# 04B-356.net
KiCad netlist of a schematic drawn in EAGLE
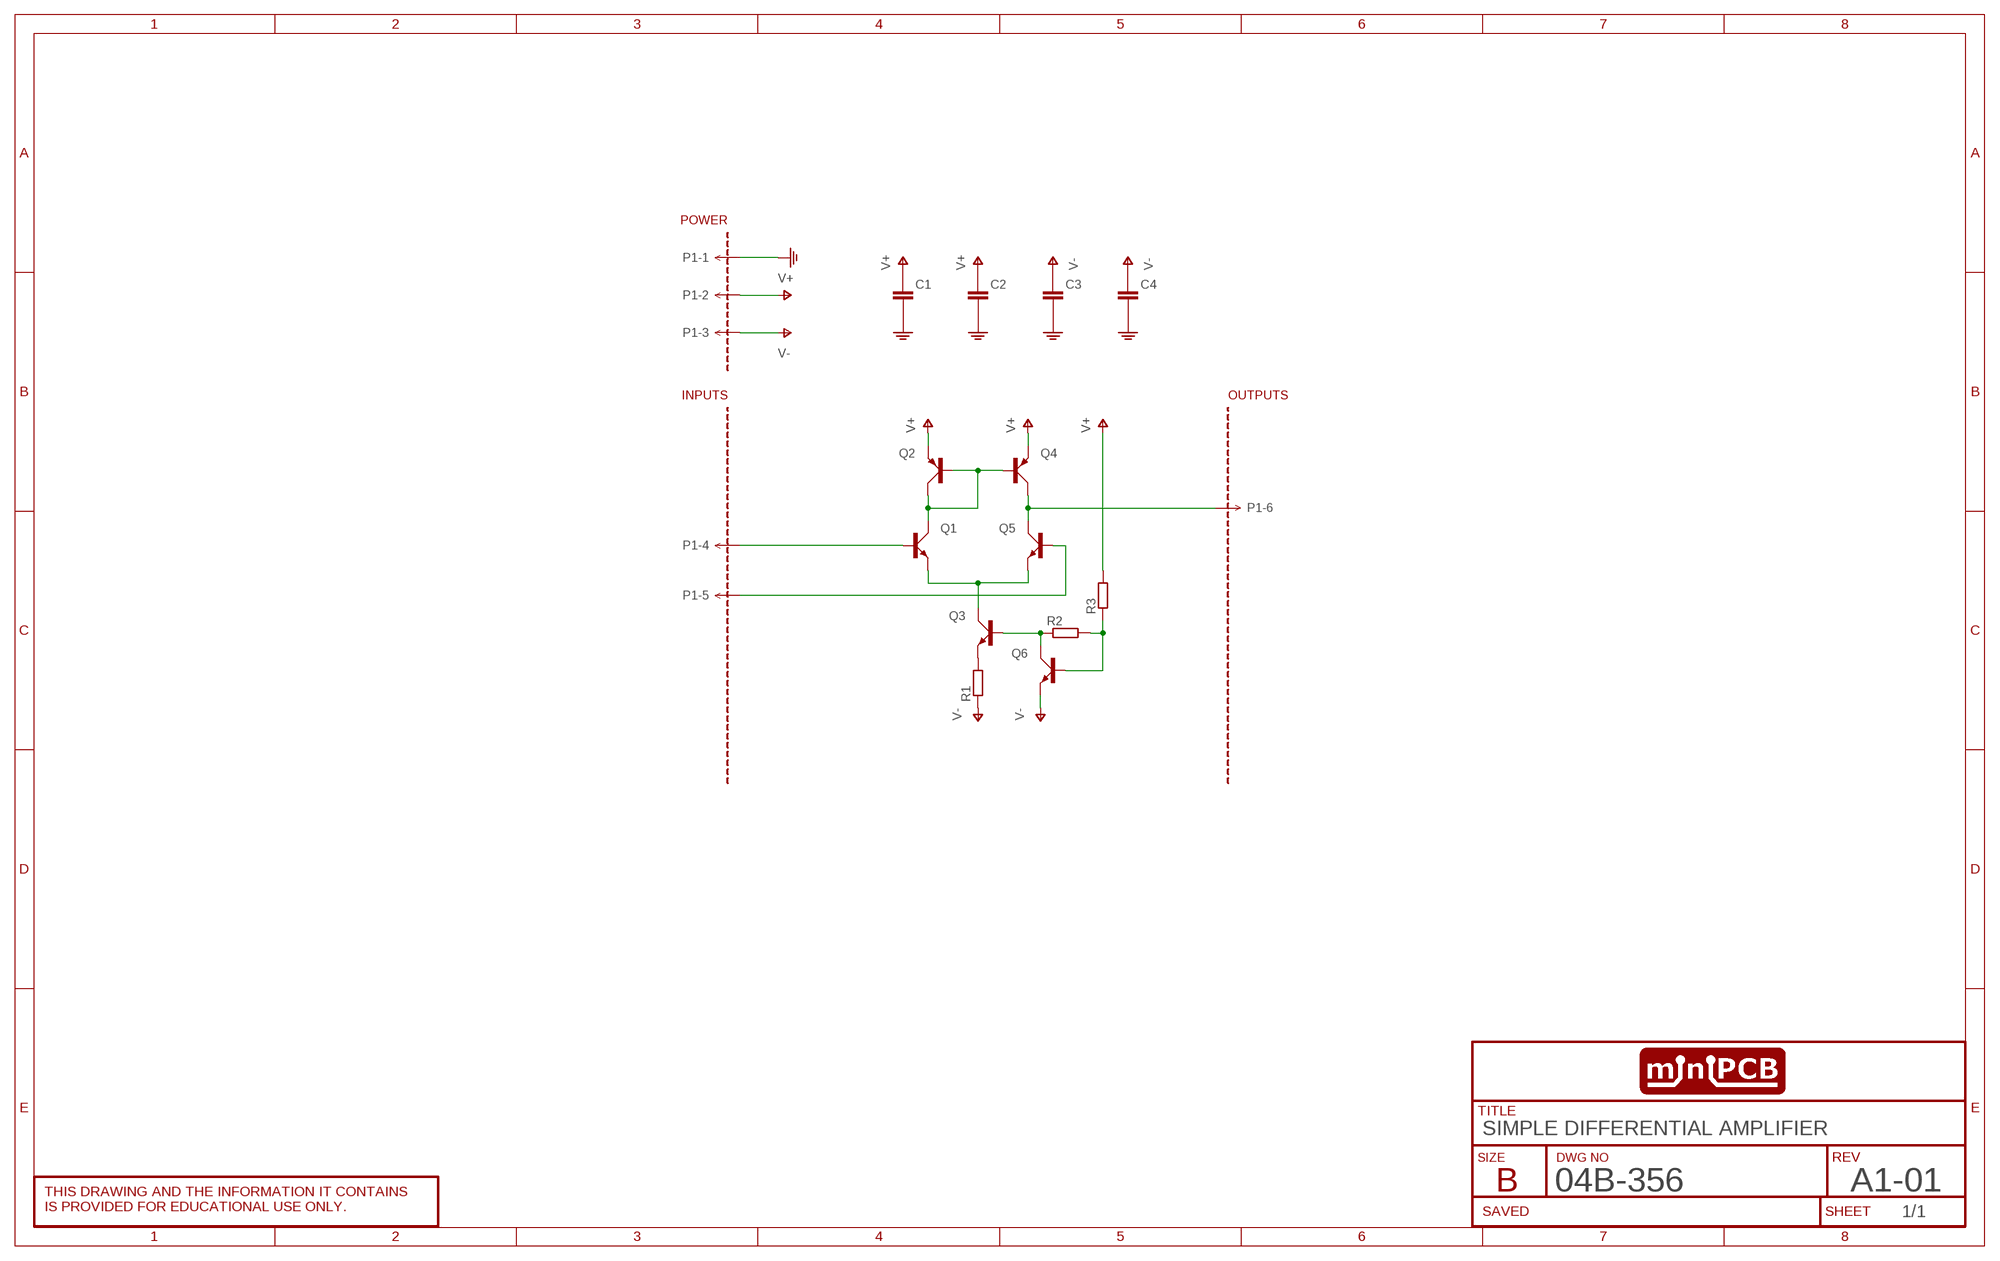
[diagram p0: schematic, sheet 1]

(export (version "E")
  (design (tool "Eeschema 10.0.6"))
  (components
    (comp (ref "C1")
      (value "CAPACITORSMD")
      (footprint "eagle-import:C0805")
      (libsource (lib "eagle-import") (part "CAPACITORSMD"))
    )
    (comp (ref "C2")
      (value "CAPACITORSMD")
      (footprint "eagle-import:C0805")
      (libsource (lib "eagle-import") (part "CAPACITORSMD"))
    )
    (comp (ref "C3")
      (value "CAPACITORSMD")
      (footprint "eagle-import:C0805")
      (libsource (lib "eagle-import") (part "CAPACITORSMD"))
    )
    (comp (ref "C4")
      (value "CAPACITORSMD")
      (footprint "eagle-import:C0805")
      (libsource (lib "eagle-import") (part "CAPACITORSMD"))
    )
    (comp (ref "P1")
      (value "MINIPCB_6P")
      (footprint "eagle-import:PINS_6")
      (libsource (lib "eagle-import") (part "MINIPCB_6P"))
    )
    (comp (ref "PCB1")
      (value "MINIPCB_0PPCB33-20")
      (footprint "eagle-import:PCB33-20")
      (fields (field (name "PART_NUMBER") "04B-356") (field (name "TITLE") "SIMPLE DIFF. AMP."))
      (libsource (lib "eagle-import") (part "MINIPCB_0PPCB33-20"))
    )
    (comp (ref "Q1")
      (value "BJT_NPNBEC")
      (footprint "eagle-import:SOT23")
      (libsource (lib "eagle-import") (part "BJT_NPNBEC"))
    )
    (comp (ref "Q2")
      (value "BJT_PNPBEC")
      (footprint "eagle-import:SOT23")
      (libsource (lib "eagle-import") (part "BJT_PNPBEC"))
    )
    (comp (ref "Q3")
      (value "BJT_NPNBEC")
      (footprint "eagle-import:SOT23")
      (libsource (lib "eagle-import") (part "BJT_NPNBEC"))
    )
    (comp (ref "Q4")
      (value "BJT_PNPBEC")
      (footprint "eagle-import:SOT23")
      (libsource (lib "eagle-import") (part "BJT_PNPBEC"))
    )
    (comp (ref "Q5")
      (value "BJT_NPNBEC")
      (footprint "eagle-import:SOT23")
      (libsource (lib "eagle-import") (part "BJT_NPNBEC"))
    )
    (comp (ref "Q6")
      (value "BJT_NPNBEC")
      (footprint "eagle-import:SOT23")
      (libsource (lib "eagle-import") (part "BJT_NPNBEC"))
    )
    (comp (ref "R1")
      (value "RESISTORSMD")
      (footprint "eagle-import:R0805")
      (libsource (lib "eagle-import") (part "RESISTORSMD"))
    )
    (comp (ref "R2")
      (value "RESISTORSMD")
      (footprint "eagle-import:R0805")
      (libsource (lib "eagle-import") (part "RESISTORSMD"))
    )
    (comp (ref "R3")
      (value "RESISTORSMD")
      (footprint "eagle-import:R0805")
      (libsource (lib "eagle-import") (part "RESISTORSMD"))
    )
  )
  (nets
    (net (code "1") (name "GND") (class "Default")
      (node (ref "C1") (pin "2ASDF") (pinfunction "-_2ASDF") (pintype "passive"))
      (node (ref "C2") (pin "2ASDF") (pinfunction "-_2ASDF") (pintype "passive"))
      (node (ref "C3") (pin "2ASDF") (pinfunction "-_2ASDF") (pintype "passive"))
      (node (ref "C4") (pin "2ASDF") (pinfunction "-_2ASDF") (pintype "passive"))
      (node (ref "P1") (pin "1") (pinfunction "1_1") (pintype "bidirectional"))
    )
    (net (code "2") (name "Net-(P1D-1)") (class "Default")
      (node (ref "P1") (pin "4") (pinfunction "1_4") (pintype "bidirectional"))
      (node (ref "Q1") (pin "1") (pinfunction "B_1") (pintype "passive"))
    )
    (net (code "3") (name "Net-(P1E-1)") (class "Default")
      (node (ref "P1") (pin "5") (pinfunction "1_5") (pintype "bidirectional"))
      (node (ref "Q5") (pin "1") (pinfunction "B_1") (pintype "passive"))
    )
    (net (code "4") (name "Net-(P1F-1)") (class "Default")
      (node (ref "P1") (pin "6") (pinfunction "1_6") (pintype "bidirectional"))
      (node (ref "Q4") (pin "3") (pinfunction "C_3") (pintype "passive"))
      (node (ref "Q5") (pin "3") (pinfunction "C_3") (pintype "passive"))
    )
    (net (code "5") (name "Net-(Q1-C)") (class "Default")
      (node (ref "Q1") (pin "3") (pinfunction "C_3") (pintype "passive"))
      (node (ref "Q2") (pin "1") (pinfunction "B_1") (pintype "passive"))
      (node (ref "Q2") (pin "3") (pinfunction "C_3") (pintype "passive"))
      (node (ref "Q4") (pin "1") (pinfunction "B_1") (pintype "passive"))
    )
    (net (code "6") (name "Net-(Q1-E)") (class "Default")
      (node (ref "Q1") (pin "2") (pinfunction "E_2") (pintype "passive"))
      (node (ref "Q3") (pin "3") (pinfunction "C_3") (pintype "passive"))
      (node (ref "Q5") (pin "2") (pinfunction "E_2") (pintype "passive"))
    )
    (net (code "7") (name "Net-(Q3-B)") (class "Default")
      (node (ref "Q3") (pin "1") (pinfunction "B_1") (pintype "passive"))
      (node (ref "Q6") (pin "3") (pinfunction "C_3") (pintype "passive"))
      (node (ref "R2") (pin "1") (pinfunction "1_1") (pintype "passive"))
    )
    (net (code "8") (name "Net-(Q3-E)") (class "Default")
      (node (ref "Q3") (pin "2") (pinfunction "E_2") (pintype "passive"))
      (node (ref "R1") (pin "2") (pinfunction "2_2") (pintype "passive"))
    )
    (net (code "9") (name "Net-(Q6-B)") (class "Default")
      (node (ref "Q6") (pin "1") (pinfunction "B_1") (pintype "passive"))
      (node (ref "R2") (pin "2") (pinfunction "2_2") (pintype "passive"))
      (node (ref "R3") (pin "1") (pinfunction "1_1") (pintype "passive"))
    )
    (net (code "10") (name "V+") (class "Default")
      (node (ref "C1") (pin "1ASD") (pinfunction "+_1ASD") (pintype "passive"))
      (node (ref "C2") (pin "1ASD") (pinfunction "+_1ASD") (pintype "passive"))
      (node (ref "P1") (pin "2") (pinfunction "1_2") (pintype "bidirectional"))
      (node (ref "Q2") (pin "2") (pinfunction "E_2") (pintype "passive"))
      (node (ref "Q4") (pin "2") (pinfunction "E_2") (pintype "passive"))
      (node (ref "R3") (pin "2") (pinfunction "2_2") (pintype "passive"))
    )
    (net (code "11") (name "V-") (class "Default")
      (node (ref "C3") (pin "1ASD") (pinfunction "+_1ASD") (pintype "passive"))
      (node (ref "C4") (pin "1ASD") (pinfunction "+_1ASD") (pintype "passive"))
      (node (ref "P1") (pin "3") (pinfunction "1_3") (pintype "bidirectional"))
      (node (ref "Q6") (pin "2") (pinfunction "E_2") (pintype "passive"))
      (node (ref "R1") (pin "1") (pinfunction "1_1") (pintype "passive"))
    )
  )
)
